# tesla3rtm.net
KiCad netlist of a schematic drawn in EAGLE
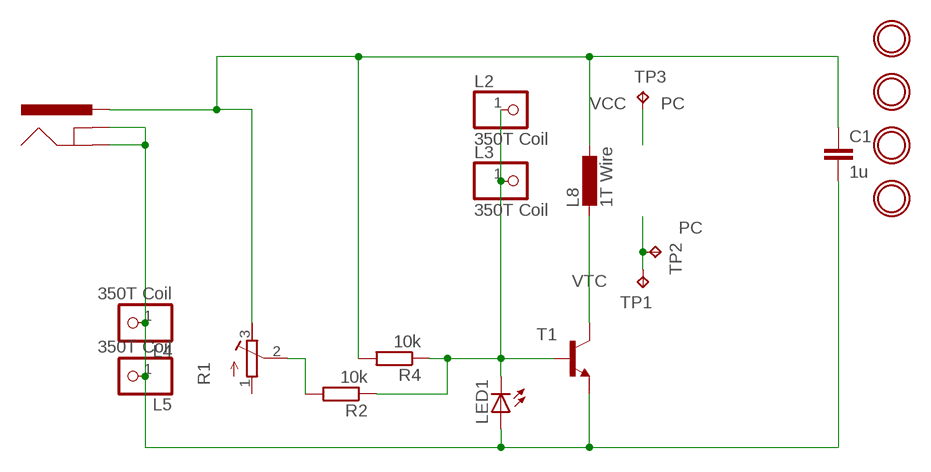
[diagram p0: schematic, sheet 1]

(export (version "E")
  (design (tool "Eeschema 10.0.6"))
  (components
    (comp (ref "C1")
      (value "1u")
      (footprint "eagle-import:C050-025X075")
      (libsource (lib "eagle-import") (part "C-EU050-025X075"))
    )
    (comp (ref "J1")
      (value "POWER_JACKPTH")
      (footprint "eagle-import:POWER_JACK_PTH")
      (libsource (lib "eagle-import") (part "POWER_JACKPTH"))
    )
    (comp (ref "L2")
      (value "350T Coil")
      (footprint "eagle-import:1X01")
      (libsource (lib "eagle-import") (part "PINHD-1X1"))
    )
    (comp (ref "L3")
      (value "350T Coil")
      (footprint "eagle-import:1X01")
      (libsource (lib "eagle-import") (part "PINHD-1X1"))
    )
    (comp (ref "L4")
      (value "350T Coil")
      (footprint "eagle-import:1X01")
      (libsource (lib "eagle-import") (part "PINHD-1X1"))
    )
    (comp (ref "L5")
      (value "350T Coil")
      (footprint "eagle-import:1X01")
      (libsource (lib "eagle-import") (part "PINHD-1X1"))
    )
    (comp (ref "L8")
      (value "1T Wire")
      (footprint "eagle-import:0204_7")
      (libsource (lib "eagle-import") (part "L-EU0204/7"))
    )
    (comp (ref "LED1")
      (value "LED3MM")
      (footprint "eagle-import:LED3MM")
      (libsource (lib "eagle-import") (part "LED3MM"))
    )
    (comp (ref "R1")
      (value "R-TRIMM3339P")
      (footprint "eagle-import:RTRIM3339P")
      (libsource (lib "eagle-import") (part "R-TRIMM3339P"))
    )
    (comp (ref "R2")
      (value "10k")
      (footprint "eagle-import:0207_7")
      (libsource (lib "eagle-import") (part "R-EU_0207/7"))
    )
    (comp (ref "R4")
      (value "10k")
      (footprint "eagle-import:0207_7")
      (libsource (lib "eagle-import") (part "R-EU_0207/7"))
    )
    (comp (ref "T1")
      (value "-NPN-TO220")
      (footprint "eagle-import:TO220")
      (libsource (lib "eagle-import") (part "-NPN-TO220"))
    )
    (comp (ref "TP1")
      (value "TPTP20SQ")
      (footprint "eagle-import:TP20SQ")
      (libsource (lib "eagle-import") (part "TPTP20SQ"))
    )
    (comp (ref "TP2")
      (value "TPTP16R")
      (footprint "eagle-import:TP16R")
      (libsource (lib "eagle-import") (part "TPTP16R"))
    )
    (comp (ref "TP3")
      (value "TPTP20R")
      (footprint "eagle-import:TP20R")
      (libsource (lib "eagle-import") (part "TPTP20R"))
    )
    (comp (ref "U$1")
      (value "MOUNTINGHOLE3.0THIN")
      (footprint "eagle-import:MOUNTINGHOLE_3.0_PLATEDTHIN")
      (libsource (lib "eagle-import") (part "MOUNTINGHOLE3.0THIN"))
    )
    (comp (ref "U$2")
      (value "MOUNTINGHOLE3.0THIN")
      (footprint "eagle-import:MOUNTINGHOLE_3.0_PLATEDTHIN")
      (libsource (lib "eagle-import") (part "MOUNTINGHOLE3.0THIN"))
    )
    (comp (ref "U$3")
      (value "MOUNTINGHOLE3.0THIN")
      (footprint "eagle-import:MOUNTINGHOLE_3.0_PLATEDTHIN")
      (libsource (lib "eagle-import") (part "MOUNTINGHOLE3.0THIN"))
    )
    (comp (ref "U$4")
      (value "MOUNTINGHOLE3.0THIN")
      (footprint "eagle-import:MOUNTINGHOLE_3.0_PLATEDTHIN")
      (libsource (lib "eagle-import") (part "MOUNTINGHOLE3.0THIN"))
    )
  )
  (nets
    (net (code "1") (name "/PC") (class "Default")
      (node (ref "TP1") (pin "TP") (pinfunction "TP_TP") (pintype "input"))
      (node (ref "TP2") (pin "TP") (pinfunction "TP_TP") (pintype "input"))
      (node (ref "TP3") (pin "TP") (pinfunction "TP_TP") (pintype "input"))
    )
    (net (code "2") (name "/VCC") (class "Default")
      (node (ref "C1") (pin "1") (pinfunction "1_1") (pintype "passive"))
      (node (ref "J1") (pin "PWR") (pinfunction "PWR_PWR") (pintype "bidirectional"))
      (node (ref "L8") (pin "1") (pinfunction "1_1") (pintype "passive"))
      (node (ref "R1") (pin "3") (pinfunction "E_3") (pintype "passive"))
      (node (ref "R4") (pin "2") (pinfunction "2_2") (pintype "passive"))
    )
    (net (code "3") (name "/VTC") (class "Default")
      (node (ref "L8") (pin "2") (pinfunction "2_2") (pintype "passive"))
      (node (ref "T1") (pin "2") (pinfunction "C_2") (pintype "passive"))
    )
    (net (code "4") (name "Net-(LED1-C)") (class "Default")
      (node (ref "L2") (pin "1") (pinfunction "1_1") (pintype "passive"))
      (node (ref "L3") (pin "1") (pinfunction "1_1") (pintype "passive"))
      (node (ref "LED1") (pin "K") (pinfunction "C_K") (pintype "passive"))
      (node (ref "R2") (pin "1") (pinfunction "1_1") (pintype "passive"))
      (node (ref "R4") (pin "1") (pinfunction "1_1") (pintype "passive"))
      (node (ref "T1") (pin "1") (pinfunction "B_1") (pintype "passive"))
    )
    (net (code "5") (name "Net-(R1-S)") (class "Default")
      (node (ref "R1") (pin "2") (pinfunction "S_2") (pintype "passive"))
      (node (ref "R2") (pin "2") (pinfunction "2_2") (pintype "passive"))
    )
    (net (code "6") (name "Net-(T1-E)") (class "Default")
      (node (ref "C1") (pin "2") (pinfunction "2_2") (pintype "passive"))
      (node (ref "J1") (pin "GND") (pinfunction "GND_GND") (pintype "bidirectional"))
      (node (ref "J1") (pin "GNDBREAK") (pinfunction "GNDBREAK_GNDBREAK") (pintype "bidirectional"))
      (node (ref "L4") (pin "1") (pinfunction "1_1") (pintype "passive"))
      (node (ref "L5") (pin "1") (pinfunction "1_1") (pintype "passive"))
      (node (ref "LED1") (pin "A") (pinfunction "A_A") (pintype "passive"))
      (node (ref "T1") (pin "3") (pinfunction "E_3") (pintype "passive"))
    )
    (net (code "7") (name "unconnected-(R1-A-Pad1)") (class "Default")
      (node (ref "R1") (pin "1") (pinfunction "A_1") (pintype "passive"))
    )
  )
)
